# aw_201_clock.net
KiCad netlist of a schematic drawn in EAGLE
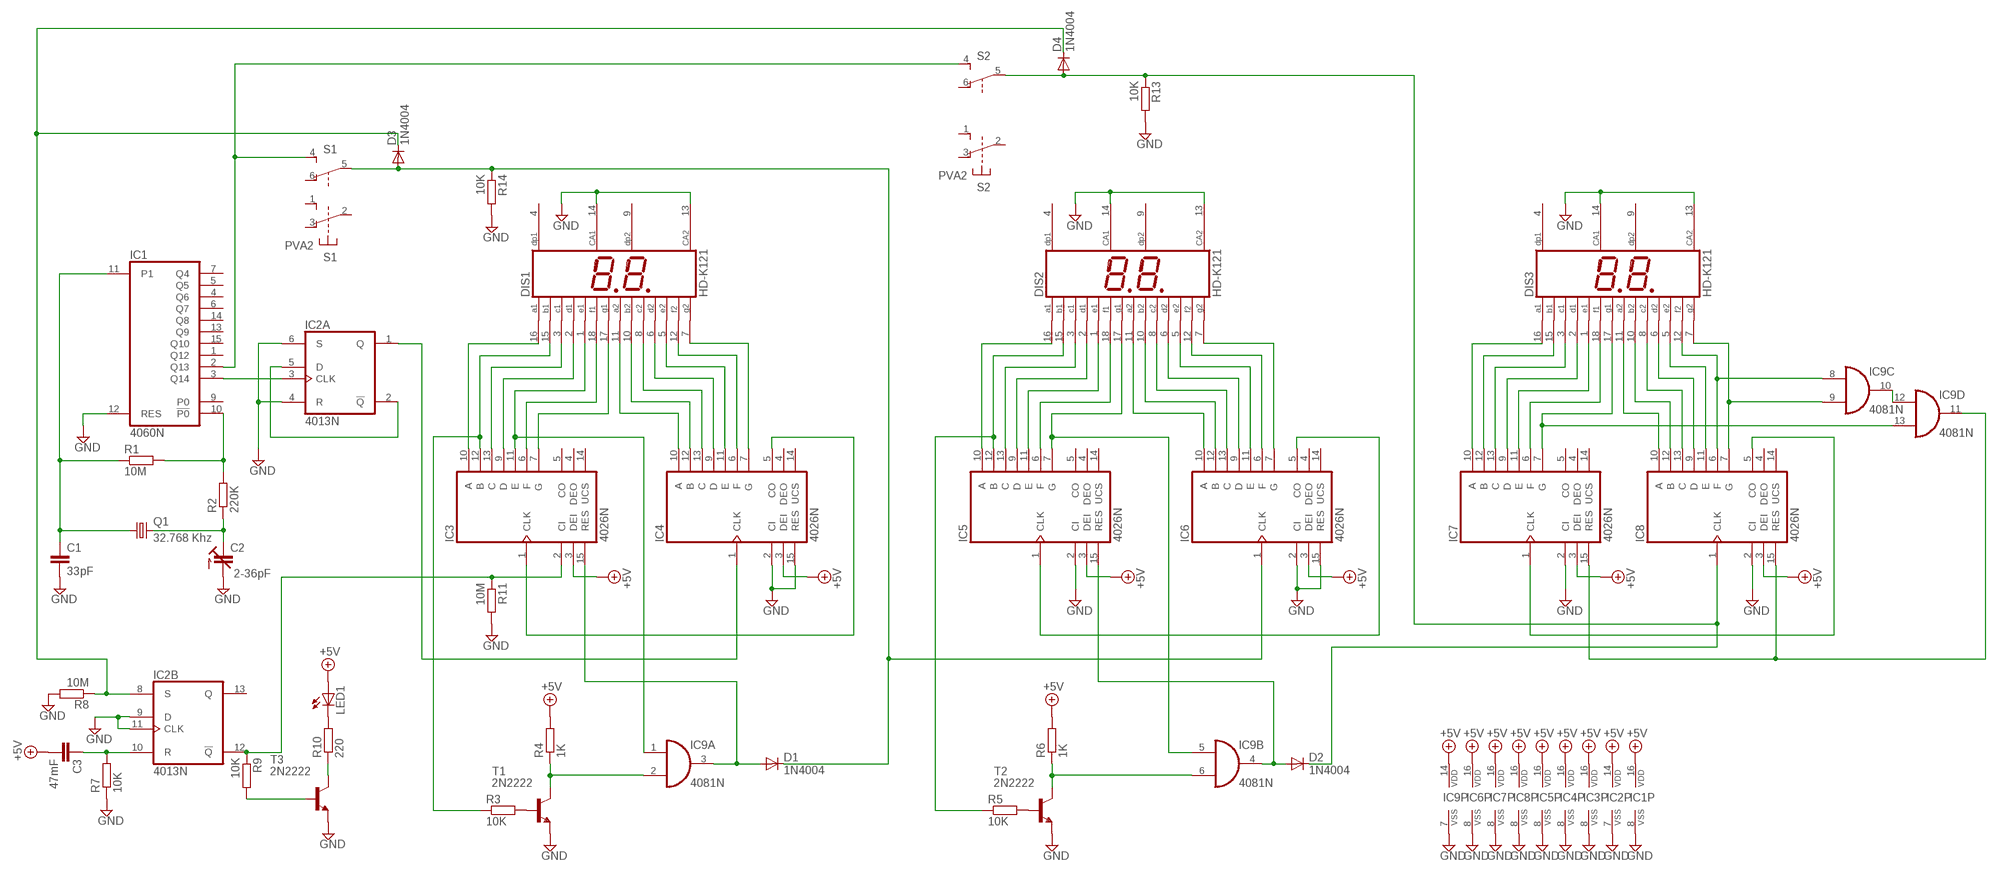
[diagram p0: schematic, sheet 1]

(export (version "E")
  (design (tool "Eeschema 10.0.6"))
  (components
    (comp (ref "C1")
      (value "33pF")
      (footprint "eagle-import:C050-024X044")
      (libsource (lib "eagle-import") (part "C-EU050-024X044"))
    )
    (comp (ref "C2")
      (value "2-36pF")
      (footprint "eagle-import:CTRIM3050.504")
      (libsource (lib "eagle-import") (part "C-TRIMM3050.504"))
    )
    (comp (ref "C3")
      (value "47mF")
      (footprint "eagle-import:C050-024X044")
      (libsource (lib "eagle-import") (part "C-EU050-024X044"))
    )
    (comp (ref "D1")
      (value "1N4004")
      (footprint "eagle-import:DO41-10")
      (libsource (lib "eagle-import") (part "1N4004"))
    )
    (comp (ref "D2")
      (value "1N4004")
      (footprint "eagle-import:DO41-10")
      (libsource (lib "eagle-import") (part "1N4004"))
    )
    (comp (ref "D3")
      (value "1N4004")
      (footprint "eagle-import:DO41-10")
      (libsource (lib "eagle-import") (part "1N4004"))
    )
    (comp (ref "D4")
      (value "1N4004")
      (footprint "eagle-import:DO41-10")
      (libsource (lib "eagle-import") (part "1N4004"))
    )
    (comp (ref "DIS1")
      (value "HD-K121")
      (footprint "eagle-import:HDSP-R")
      (libsource (lib "eagle-import") (part "HD-K121"))
    )
    (comp (ref "DIS2")
      (value "HD-K121")
      (footprint "eagle-import:HDSP-R")
      (libsource (lib "eagle-import") (part "HD-K121"))
    )
    (comp (ref "DIS3")
      (value "HD-K121")
      (footprint "eagle-import:HDSP-R")
      (libsource (lib "eagle-import") (part "HD-K121"))
    )
    (comp (ref "IC1")
      (value "4060N")
      (footprint "eagle-import:DIL16")
      (libsource (lib "eagle-import") (part "4060N"))
    )
    (comp (ref "IC2")
      (value "4013N")
      (footprint "eagle-import:DIL14")
      (libsource (lib "eagle-import") (part "4013N"))
    )
    (comp (ref "IC3")
      (value "4026N")
      (footprint "eagle-import:DIL16")
      (libsource (lib "eagle-import") (part "4026N"))
    )
    (comp (ref "IC4")
      (value "4026N")
      (footprint "eagle-import:DIL16")
      (libsource (lib "eagle-import") (part "4026N"))
    )
    (comp (ref "IC5")
      (value "4026N")
      (footprint "eagle-import:DIL16")
      (libsource (lib "eagle-import") (part "4026N"))
    )
    (comp (ref "IC6")
      (value "4026N")
      (footprint "eagle-import:DIL16")
      (libsource (lib "eagle-import") (part "4026N"))
    )
    (comp (ref "IC7")
      (value "4026N")
      (footprint "eagle-import:DIL16")
      (libsource (lib "eagle-import") (part "4026N"))
    )
    (comp (ref "IC8")
      (value "4026N")
      (footprint "eagle-import:DIL16")
      (libsource (lib "eagle-import") (part "4026N"))
    )
    (comp (ref "IC9")
      (value "4081N")
      (footprint "eagle-import:DIL14")
      (libsource (lib "eagle-import") (part "4081N"))
    )
    (comp (ref "LED1")
      (value "LED5MM")
      (footprint "eagle-import:LED5MM")
      (libsource (lib "eagle-import") (part "LED5MM"))
    )
    (comp (ref "Q1")
      (value "32.768 Khz")
      (footprint "eagle-import:TC26V")
      (libsource (lib "eagle-import") (part "CRYSTALTC26V"))
    )
    (comp (ref "R1")
      (value "10M")
      (footprint "eagle-import:0207_10")
      (libsource (lib "eagle-import") (part "R-EU_0207/10"))
    )
    (comp (ref "R2")
      (value "220K")
      (footprint "eagle-import:0207_10")
      (libsource (lib "eagle-import") (part "R-EU_0207/10"))
    )
    (comp (ref "R3")
      (value "10K")
      (footprint "eagle-import:0207_10")
      (libsource (lib "eagle-import") (part "R-EU_0207/10"))
    )
    (comp (ref "R4")
      (value "1K")
      (footprint "eagle-import:0207_10")
      (libsource (lib "eagle-import") (part "R-EU_0207/10"))
    )
    (comp (ref "R5")
      (value "10K")
      (footprint "eagle-import:0207_10")
      (libsource (lib "eagle-import") (part "R-EU_0207/10"))
    )
    (comp (ref "R6")
      (value "1K")
      (footprint "eagle-import:0207_10")
      (libsource (lib "eagle-import") (part "R-EU_0207/10"))
    )
    (comp (ref "R7")
      (value "10K")
      (footprint "eagle-import:0207_10")
      (libsource (lib "eagle-import") (part "R-EU_0207/10"))
    )
    (comp (ref "R8")
      (value "10M")
      (footprint "eagle-import:0207_10")
      (libsource (lib "eagle-import") (part "R-EU_0207/10"))
    )
    (comp (ref "R9")
      (value "10K")
      (footprint "eagle-import:0207_10")
      (libsource (lib "eagle-import") (part "R-EU_0207/10"))
    )
    (comp (ref "R10")
      (value "220")
      (footprint "eagle-import:0207_10")
      (libsource (lib "eagle-import") (part "R-EU_0207/10"))
    )
    (comp (ref "R11")
      (value "10M")
      (footprint "eagle-import:0207_10")
      (libsource (lib "eagle-import") (part "R-EU_0207/10"))
    )
    (comp (ref "R13")
      (value "10K")
      (footprint "eagle-import:0207_10")
      (libsource (lib "eagle-import") (part "R-EU_0207/10"))
    )
    (comp (ref "R14")
      (value "10K")
      (footprint "eagle-import:0207_10")
      (libsource (lib "eagle-import") (part "R-EU_0207/10"))
    )
    (comp (ref "S1")
      (value "PVA2")
      (footprint "eagle-import:PVA2F")
      (libsource (lib "eagle-import") (part "PVA2"))
    )
    (comp (ref "S2")
      (value "PVA2")
      (footprint "eagle-import:PVA2F")
      (libsource (lib "eagle-import") (part "PVA2"))
    )
    (comp (ref "T1")
      (value "2N2222")
      (footprint "eagle-import:TO18")
      (libsource (lib "eagle-import") (part "2N2222"))
    )
    (comp (ref "T2")
      (value "2N2222")
      (footprint "eagle-import:TO18")
      (libsource (lib "eagle-import") (part "2N2222"))
    )
    (comp (ref "T3")
      (value "2N2222")
      (footprint "eagle-import:TO18")
      (libsource (lib "eagle-import") (part "2N2222"))
    )
  )
  (nets
    (net (code "1") (name "+5V") (class "Default")
      (node (ref "C3") (pin "2") (pinfunction "2_2") (pintype "passive"))
      (node (ref "IC1") (pin "16") (pinfunction "VDD_16") (pintype "power_in"))
      (node (ref "IC2") (pin "14") (pinfunction "VDD_14") (pintype "power_in"))
      (node (ref "IC3") (pin "16") (pinfunction "VDD_16") (pintype "power_in"))
      (node (ref "IC3") (pin "3") (pinfunction "DEI_3") (pintype "input"))
      (node (ref "IC4") (pin "16") (pinfunction "VDD_16") (pintype "power_in"))
      (node (ref "IC4") (pin "3") (pinfunction "DEI_3") (pintype "input"))
      (node (ref "IC5") (pin "16") (pinfunction "VDD_16") (pintype "power_in"))
      (node (ref "IC5") (pin "3") (pinfunction "DEI_3") (pintype "input"))
      (node (ref "IC6") (pin "16") (pinfunction "VDD_16") (pintype "power_in"))
      (node (ref "IC6") (pin "3") (pinfunction "DEI_3") (pintype "input"))
      (node (ref "IC7") (pin "16") (pinfunction "VDD_16") (pintype "power_in"))
      (node (ref "IC7") (pin "3") (pinfunction "DEI_3") (pintype "input"))
      (node (ref "IC8") (pin "16") (pinfunction "VDD_16") (pintype "power_in"))
      (node (ref "IC8") (pin "3") (pinfunction "DEI_3") (pintype "input"))
      (node (ref "IC9") (pin "14") (pinfunction "VDD_14") (pintype "power_in"))
      (node (ref "LED1") (pin "A") (pinfunction "A_A") (pintype "passive"))
      (node (ref "R4") (pin "2") (pinfunction "2_2") (pintype "passive"))
      (node (ref "R6") (pin "2") (pinfunction "2_2") (pintype "passive"))
    )
    (net (code "2") (name "GND") (class "Default")
      (node (ref "C1") (pin "2") (pinfunction "2_2") (pintype "passive"))
      (node (ref "C2") (pin "2") (pinfunction "A_2") (pintype "passive"))
      (node (ref "DIS1") (pin "13") (pinfunction "CA2_13") (pintype "passive"))
      (node (ref "DIS1") (pin "14") (pinfunction "CA1_14") (pintype "passive"))
      (node (ref "DIS2") (pin "13") (pinfunction "CA2_13") (pintype "passive"))
      (node (ref "DIS2") (pin "14") (pinfunction "CA1_14") (pintype "passive"))
      (node (ref "DIS3") (pin "13") (pinfunction "CA2_13") (pintype "passive"))
      (node (ref "DIS3") (pin "14") (pinfunction "CA1_14") (pintype "passive"))
      (node (ref "IC1") (pin "12") (pinfunction "RES_12") (pintype "input"))
      (node (ref "IC1") (pin "8") (pinfunction "VSS_8") (pintype "power_in"))
      (node (ref "IC2") (pin "11") (pinfunction "CLK_11") (pintype "input"))
      (node (ref "IC2") (pin "4") (pinfunction "R_4") (pintype "input"))
      (node (ref "IC2") (pin "6") (pinfunction "S_6") (pintype "input"))
      (node (ref "IC2") (pin "7") (pinfunction "VSS_7") (pintype "power_in"))
      (node (ref "IC2") (pin "9") (pinfunction "D_9") (pintype "input"))
      (node (ref "IC3") (pin "8") (pinfunction "VSS_8") (pintype "power_in"))
      (node (ref "IC4") (pin "15") (pinfunction "RES_15") (pintype "input"))
      (node (ref "IC4") (pin "2") (pinfunction "CI_2") (pintype "input"))
      (node (ref "IC4") (pin "8") (pinfunction "VSS_8") (pintype "power_in"))
      (node (ref "IC5") (pin "2") (pinfunction "CI_2") (pintype "input"))
      (node (ref "IC5") (pin "8") (pinfunction "VSS_8") (pintype "power_in"))
      (node (ref "IC6") (pin "15") (pinfunction "RES_15") (pintype "input"))
      (node (ref "IC6") (pin "2") (pinfunction "CI_2") (pintype "input"))
      (node (ref "IC6") (pin "8") (pinfunction "VSS_8") (pintype "power_in"))
      (node (ref "IC7") (pin "2") (pinfunction "CI_2") (pintype "input"))
      (node (ref "IC7") (pin "8") (pinfunction "VSS_8") (pintype "power_in"))
      (node (ref "IC8") (pin "2") (pinfunction "CI_2") (pintype "input"))
      (node (ref "IC8") (pin "8") (pinfunction "VSS_8") (pintype "power_in"))
      (node (ref "IC9") (pin "7") (pinfunction "VSS_7") (pintype "power_in"))
      (node (ref "R11") (pin "2") (pinfunction "2_2") (pintype "passive"))
      (node (ref "R13") (pin "2") (pinfunction "2_2") (pintype "passive"))
      (node (ref "R14") (pin "2") (pinfunction "2_2") (pintype "passive"))
      (node (ref "R7") (pin "1") (pinfunction "1_1") (pintype "passive"))
      (node (ref "R8") (pin "2") (pinfunction "2_2") (pintype "passive"))
      (node (ref "T1") (pin "1") (pinfunction "E_1") (pintype "passive"))
      (node (ref "T2") (pin "1") (pinfunction "E_1") (pintype "passive"))
      (node (ref "T3") (pin "1") (pinfunction "E_1") (pintype "passive"))
    )
    (net (code "3") (name "Net-(C2-E)") (class "Default")
      (node (ref "C2") (pin "1") (pinfunction "E_1") (pintype "passive"))
      (node (ref "Q1") (pin "2") (pinfunction "2_2") (pintype "passive"))
      (node (ref "R2") (pin "1") (pinfunction "1_1") (pintype "passive"))
    )
    (net (code "4") (name "Net-(DIS1-A1)") (class "Default")
      (node (ref "DIS1") (pin "16") (pinfunction "A1_16") (pintype "passive"))
      (node (ref "IC3") (pin "10") (pinfunction "A_10") (pintype "output"))
    )
    (net (code "5") (name "Net-(DIS1-A2)") (class "Default")
      (node (ref "DIS1") (pin "11") (pinfunction "A2_11") (pintype "passive"))
      (node (ref "IC4") (pin "10") (pinfunction "A_10") (pintype "output"))
    )
    (net (code "6") (name "Net-(DIS1-B1)") (class "Default")
      (node (ref "DIS1") (pin "15") (pinfunction "B1_15") (pintype "passive"))
      (node (ref "IC3") (pin "12") (pinfunction "B_12") (pintype "output"))
      (node (ref "R3") (pin "1") (pinfunction "1_1") (pintype "passive"))
    )
    (net (code "7") (name "Net-(DIS1-B2)") (class "Default")
      (node (ref "DIS1") (pin "10") (pinfunction "B2_10") (pintype "passive"))
      (node (ref "IC4") (pin "12") (pinfunction "B_12") (pintype "output"))
    )
    (net (code "8") (name "Net-(DIS1-C1)") (class "Default")
      (node (ref "DIS1") (pin "3") (pinfunction "C1_3") (pintype "passive"))
      (node (ref "IC3") (pin "13") (pinfunction "C_13") (pintype "output"))
    )
    (net (code "9") (name "Net-(DIS1-C2)") (class "Default")
      (node (ref "DIS1") (pin "8") (pinfunction "C2_8") (pintype "passive"))
      (node (ref "IC4") (pin "13") (pinfunction "C_13") (pintype "output"))
    )
    (net (code "10") (name "Net-(DIS1-D1)") (class "Default")
      (node (ref "DIS1") (pin "2") (pinfunction "D1_2") (pintype "passive"))
      (node (ref "IC3") (pin "9") (pinfunction "D_9") (pintype "output"))
    )
    (net (code "11") (name "Net-(DIS1-D2)") (class "Default")
      (node (ref "DIS1") (pin "6") (pinfunction "D2_6") (pintype "passive"))
      (node (ref "IC4") (pin "9") (pinfunction "D_9") (pintype "output"))
    )
    (net (code "12") (name "Net-(DIS1-E1)") (class "Default")
      (node (ref "DIS1") (pin "1") (pinfunction "E1_1") (pintype "passive"))
      (node (ref "IC3") (pin "11") (pinfunction "E_11") (pintype "output"))
      (node (ref "IC9") (pin "1") (pinfunction "I0_1") (pintype "input"))
    )
    (net (code "13") (name "Net-(DIS1-E2)") (class "Default")
      (node (ref "DIS1") (pin "5") (pinfunction "E2_5") (pintype "passive"))
      (node (ref "IC4") (pin "11") (pinfunction "E_11") (pintype "output"))
    )
    (net (code "14") (name "Net-(DIS1-F1)") (class "Default")
      (node (ref "DIS1") (pin "18") (pinfunction "F1_18") (pintype "passive"))
      (node (ref "IC3") (pin "6") (pinfunction "F_6") (pintype "output"))
    )
    (net (code "15") (name "Net-(DIS1-F2)") (class "Default")
      (node (ref "DIS1") (pin "12") (pinfunction "F2_12") (pintype "passive"))
      (node (ref "IC4") (pin "6") (pinfunction "F_6") (pintype "output"))
    )
    (net (code "16") (name "Net-(DIS1-G1)") (class "Default")
      (node (ref "DIS1") (pin "17") (pinfunction "G1_17") (pintype "passive"))
      (node (ref "IC3") (pin "7") (pinfunction "G_7") (pintype "output"))
    )
    (net (code "17") (name "Net-(DIS1-G2)") (class "Default")
      (node (ref "DIS1") (pin "7") (pinfunction "G2_7") (pintype "passive"))
      (node (ref "IC4") (pin "7") (pinfunction "G_7") (pintype "output"))
    )
    (net (code "18") (name "Net-(DIS2-A1)") (class "Default")
      (node (ref "DIS2") (pin "16") (pinfunction "A1_16") (pintype "passive"))
      (node (ref "IC5") (pin "10") (pinfunction "A_10") (pintype "output"))
    )
    (net (code "19") (name "Net-(DIS2-A2)") (class "Default")
      (node (ref "DIS2") (pin "11") (pinfunction "A2_11") (pintype "passive"))
      (node (ref "IC6") (pin "10") (pinfunction "A_10") (pintype "output"))
    )
    (net (code "20") (name "Net-(DIS2-B1)") (class "Default")
      (node (ref "DIS2") (pin "15") (pinfunction "B1_15") (pintype "passive"))
      (node (ref "IC5") (pin "12") (pinfunction "B_12") (pintype "output"))
      (node (ref "R5") (pin "1") (pinfunction "1_1") (pintype "passive"))
    )
    (net (code "21") (name "Net-(DIS2-B2)") (class "Default")
      (node (ref "DIS2") (pin "10") (pinfunction "B2_10") (pintype "passive"))
      (node (ref "IC6") (pin "12") (pinfunction "B_12") (pintype "output"))
    )
    (net (code "22") (name "Net-(DIS2-C1)") (class "Default")
      (node (ref "DIS2") (pin "3") (pinfunction "C1_3") (pintype "passive"))
      (node (ref "IC5") (pin "13") (pinfunction "C_13") (pintype "output"))
    )
    (net (code "23") (name "Net-(DIS2-C2)") (class "Default")
      (node (ref "DIS2") (pin "8") (pinfunction "C2_8") (pintype "passive"))
      (node (ref "IC6") (pin "13") (pinfunction "C_13") (pintype "output"))
    )
    (net (code "24") (name "Net-(DIS2-D1)") (class "Default")
      (node (ref "DIS2") (pin "2") (pinfunction "D1_2") (pintype "passive"))
      (node (ref "IC5") (pin "9") (pinfunction "D_9") (pintype "output"))
    )
    (net (code "25") (name "Net-(DIS2-D2)") (class "Default")
      (node (ref "DIS2") (pin "6") (pinfunction "D2_6") (pintype "passive"))
      (node (ref "IC6") (pin "9") (pinfunction "D_9") (pintype "output"))
    )
    (net (code "26") (name "Net-(DIS2-E1)") (class "Default")
      (node (ref "DIS2") (pin "1") (pinfunction "E1_1") (pintype "passive"))
      (node (ref "IC5") (pin "11") (pinfunction "E_11") (pintype "output"))
    )
    (net (code "27") (name "Net-(DIS2-E2)") (class "Default")
      (node (ref "DIS2") (pin "5") (pinfunction "E2_5") (pintype "passive"))
      (node (ref "IC6") (pin "11") (pinfunction "E_11") (pintype "output"))
    )
    (net (code "28") (name "Net-(DIS2-F1)") (class "Default")
      (node (ref "DIS2") (pin "18") (pinfunction "F1_18") (pintype "passive"))
      (node (ref "IC5") (pin "6") (pinfunction "F_6") (pintype "output"))
    )
    (net (code "29") (name "Net-(DIS2-F2)") (class "Default")
      (node (ref "DIS2") (pin "12") (pinfunction "F2_12") (pintype "passive"))
      (node (ref "IC6") (pin "6") (pinfunction "F_6") (pintype "output"))
    )
    (net (code "30") (name "Net-(DIS2-G1)") (class "Default")
      (node (ref "DIS2") (pin "17") (pinfunction "G1_17") (pintype "passive"))
      (node (ref "IC5") (pin "7") (pinfunction "G_7") (pintype "output"))
      (node (ref "IC9") (pin "5") (pinfunction "I0_5") (pintype "input"))
    )
    (net (code "31") (name "Net-(DIS2-G2)") (class "Default")
      (node (ref "DIS2") (pin "7") (pinfunction "G2_7") (pintype "passive"))
      (node (ref "IC6") (pin "7") (pinfunction "G_7") (pintype "output"))
    )
    (net (code "32") (name "Net-(DIS3-A1)") (class "Default")
      (node (ref "DIS3") (pin "16") (pinfunction "A1_16") (pintype "passive"))
      (node (ref "IC7") (pin "10") (pinfunction "A_10") (pintype "output"))
    )
    (net (code "33") (name "Net-(DIS3-A2)") (class "Default")
      (node (ref "DIS3") (pin "11") (pinfunction "A2_11") (pintype "passive"))
      (node (ref "IC8") (pin "10") (pinfunction "A_10") (pintype "output"))
    )
    (net (code "34") (name "Net-(DIS3-B1)") (class "Default")
      (node (ref "DIS3") (pin "15") (pinfunction "B1_15") (pintype "passive"))
      (node (ref "IC7") (pin "12") (pinfunction "B_12") (pintype "output"))
    )
    (net (code "35") (name "Net-(DIS3-B2)") (class "Default")
      (node (ref "DIS3") (pin "10") (pinfunction "B2_10") (pintype "passive"))
      (node (ref "IC8") (pin "12") (pinfunction "B_12") (pintype "output"))
    )
    (net (code "36") (name "Net-(DIS3-C1)") (class "Default")
      (node (ref "DIS3") (pin "3") (pinfunction "C1_3") (pintype "passive"))
      (node (ref "IC7") (pin "13") (pinfunction "C_13") (pintype "output"))
    )
    (net (code "37") (name "Net-(DIS3-C2)") (class "Default")
      (node (ref "DIS3") (pin "8") (pinfunction "C2_8") (pintype "passive"))
      (node (ref "IC8") (pin "13") (pinfunction "C_13") (pintype "output"))
    )
    (net (code "38") (name "Net-(DIS3-D1)") (class "Default")
      (node (ref "DIS3") (pin "2") (pinfunction "D1_2") (pintype "passive"))
      (node (ref "IC7") (pin "9") (pinfunction "D_9") (pintype "output"))
    )
    (net (code "39") (name "Net-(DIS3-D2)") (class "Default")
      (node (ref "DIS3") (pin "6") (pinfunction "D2_6") (pintype "passive"))
      (node (ref "IC8") (pin "9") (pinfunction "D_9") (pintype "output"))
    )
    (net (code "40") (name "Net-(DIS3-E1)") (class "Default")
      (node (ref "DIS3") (pin "1") (pinfunction "E1_1") (pintype "passive"))
      (node (ref "IC7") (pin "11") (pinfunction "E_11") (pintype "output"))
    )
    (net (code "41") (name "Net-(DIS3-E2)") (class "Default")
      (node (ref "DIS3") (pin "5") (pinfunction "E2_5") (pintype "passive"))
      (node (ref "IC8") (pin "11") (pinfunction "E_11") (pintype "output"))
    )
    (net (code "42") (name "Net-(DIS3-F1)") (class "Default")
      (node (ref "DIS3") (pin "18") (pinfunction "F1_18") (pintype "passive"))
      (node (ref "IC7") (pin "6") (pinfunction "F_6") (pintype "output"))
    )
    (net (code "43") (name "Net-(DIS3-F2)") (class "Default")
      (node (ref "DIS3") (pin "12") (pinfunction "F2_12") (pintype "passive"))
      (node (ref "IC8") (pin "6") (pinfunction "F_6") (pintype "output"))
      (node (ref "IC9") (pin "8") (pinfunction "I0_8") (pintype "input"))
    )
    (net (code "44") (name "Net-(DIS3-G1)") (class "Default")
      (node (ref "DIS3") (pin "17") (pinfunction "G1_17") (pintype "passive"))
      (node (ref "IC7") (pin "7") (pinfunction "G_7") (pintype "output"))
      (node (ref "IC9") (pin "13") (pinfunction "I1_13") (pintype "input"))
    )
    (net (code "45") (name "Net-(DIS3-G2)") (class "Default")
      (node (ref "DIS3") (pin "7") (pinfunction "G2_7") (pintype "passive"))
      (node (ref "IC8") (pin "7") (pinfunction "G_7") (pintype "output"))
      (node (ref "IC9") (pin "9") (pinfunction "I1_9") (pintype "input"))
    )
    (net (code "46") (name "Net-(IC1A-P1)") (class "Default")
      (node (ref "C1") (pin "1") (pinfunction "1_1") (pintype "passive"))
      (node (ref "IC1") (pin "11") (pinfunction "P1_11") (pintype "input"))
      (node (ref "Q1") (pin "1") (pinfunction "1_1") (pintype "passive"))
      (node (ref "R1") (pin "1") (pinfunction "1_1") (pintype "passive"))
    )
    (net (code "47") (name "Net-(IC1A-Q13)") (class "Default")
      (node (ref "IC1") (pin "2") (pinfunction "Q13_2") (pintype "output"))
      (node (ref "S1") (pin "4") (pinfunction "S_4") (pintype "passive"))
      (node (ref "S2") (pin "4") (pinfunction "S_4") (pintype "passive"))
    )
    (net (code "48") (name "Net-(IC1A-Q14)") (class "Default")
      (node (ref "IC1") (pin "3") (pinfunction "Q14_3") (pintype "output"))
      (node (ref "IC2") (pin "3") (pinfunction "CLK_3") (pintype "input"))
    )
    (net (code "49") (name "Net-(IC1A-~{P0})") (class "Default")
      (node (ref "IC1") (pin "10") (pinfunction "~{P0}_10") (pintype "output"))
      (node (ref "R1") (pin "2") (pinfunction "2_2") (pintype "passive"))
      (node (ref "R2") (pin "2") (pinfunction "2_2") (pintype "passive"))
    )
    (net (code "50") (name "Net-(IC2A-D)") (class "Default")
      (node (ref "IC2") (pin "2") (pinfunction "~{Q}_2") (pintype "output"))
      (node (ref "IC2") (pin "5") (pinfunction "D_5") (pintype "input"))
    )
    (net (code "51") (name "Net-(IC2A-Q)") (class "Default")
      (node (ref "IC2") (pin "1") (pinfunction "Q_1") (pintype "output"))
      (node (ref "IC4") (pin "1") (pinfunction "CLK_1") (pintype "input"))
    )
    (net (code "52") (name "Net-(IC2B-R)") (class "Default")
      (node (ref "C3") (pin "1") (pinfunction "1_1") (pintype "passive"))
      (node (ref "IC2") (pin "10") (pinfunction "R_10") (pintype "input"))
      (node (ref "R7") (pin "2") (pinfunction "2_2") (pintype "passive"))
    )
    (net (code "53") (name "Net-(IC2B-S)") (class "Default")
      (node (ref "D3") (pin "C") (pinfunction "C_C") (pintype "passive"))
      (node (ref "D4") (pin "C") (pinfunction "C_C") (pintype "passive"))
      (node (ref "IC2") (pin "8") (pinfunction "S_8") (pintype "input"))
      (node (ref "R8") (pin "1") (pinfunction "1_1") (pintype "passive"))
    )
    (net (code "54") (name "Net-(IC2B-~{Q})") (class "Default")
      (node (ref "IC2") (pin "12") (pinfunction "~{Q}_12") (pintype "output"))
      (node (ref "IC3") (pin "2") (pinfunction "CI_2") (pintype "input"))
      (node (ref "R11") (pin "1") (pinfunction "1_1") (pintype "passive"))
      (node (ref "R9") (pin "1") (pinfunction "1_1") (pintype "passive"))
    )
    (net (code "55") (name "Net-(IC3A-CLK)") (class "Default")
      (node (ref "IC3") (pin "1") (pinfunction "CLK_1") (pintype "input"))
      (node (ref "IC4") (pin "5") (pinfunction "CO_5") (pintype "output"))
    )
    (net (code "56") (name "Net-(IC3A-RES)") (class "Default")
      (node (ref "D1") (pin "A") (pinfunction "A_A") (pintype "passive"))
      (node (ref "IC3") (pin "15") (pinfunction "RES_15") (pintype "input"))
      (node (ref "IC9") (pin "3") (pinfunction "O_3") (pintype "output"))
    )
    (net (code "57") (name "Net-(IC5A-CLK)") (class "Default")
      (node (ref "IC5") (pin "1") (pinfunction "CLK_1") (pintype "input"))
      (node (ref "IC6") (pin "5") (pinfunction "CO_5") (pintype "output"))
    )
    (net (code "58") (name "Net-(IC5A-RES)") (class "Default")
      (node (ref "D2") (pin "A") (pinfunction "A_A") (pintype "passive"))
      (node (ref "IC5") (pin "15") (pinfunction "RES_15") (pintype "input"))
      (node (ref "IC9") (pin "4") (pinfunction "O_4") (pintype "output"))
    )
    (net (code "59") (name "Net-(IC6A-CLK)") (class "Default")
      (node (ref "D1") (pin "C") (pinfunction "C_C") (pintype "passive"))
      (node (ref "D3") (pin "A") (pinfunction "A_A") (pintype "passive"))
      (node (ref "IC6") (pin "1") (pinfunction "CLK_1") (pintype "input"))
      (node (ref "R14") (pin "1") (pinfunction "1_1") (pintype "passive"))
      (node (ref "S1") (pin "5") (pinfunction "P_5") (pintype "passive"))
    )
    (net (code "60") (name "Net-(IC7A-CLK)") (class "Default")
      (node (ref "IC7") (pin "1") (pinfunction "CLK_1") (pintype "input"))
      (node (ref "IC8") (pin "5") (pinfunction "CO_5") (pintype "output"))
    )
    (net (code "61") (name "Net-(IC7A-RES)") (class "Default")
      (node (ref "IC7") (pin "15") (pinfunction "RES_15") (pintype "input"))
      (node (ref "IC8") (pin "15") (pinfunction "RES_15") (pintype "input"))
      (node (ref "IC9") (pin "11") (pinfunction "O_11") (pintype "output"))
    )
    (net (code "62") (name "Net-(IC8A-CLK)") (class "Default")
      (node (ref "D2") (pin "C") (pinfunction "C_C") (pintype "passive"))
      (node (ref "D4") (pin "A") (pinfunction "A_A") (pintype "passive"))
      (node (ref "IC8") (pin "1") (pinfunction "CLK_1") (pintype "input"))
      (node (ref "R13") (pin "1") (pinfunction "1_1") (pintype "passive"))
      (node (ref "S2") (pin "5") (pinfunction "P_5") (pintype "passive"))
    )
    (net (code "63") (name "Net-(IC9A-I1)") (class "Default")
      (node (ref "IC9") (pin "2") (pinfunction "I1_2") (pintype "input"))
      (node (ref "R4") (pin "1") (pinfunction "1_1") (pintype "passive"))
      (node (ref "T1") (pin "3") (pinfunction "C_3") (pintype "passive"))
    )
    (net (code "64") (name "Net-(IC9B-I1)") (class "Default")
      (node (ref "IC9") (pin "6") (pinfunction "I1_6") (pintype "input"))
      (node (ref "R6") (pin "1") (pinfunction "1_1") (pintype "passive"))
      (node (ref "T2") (pin "3") (pinfunction "C_3") (pintype "passive"))
    )
    (net (code "65") (name "Net-(IC9C-O)") (class "Default")
      (node (ref "IC9") (pin "10") (pinfunction "O_10") (pintype "output"))
      (node (ref "IC9") (pin "12") (pinfunction "I0_12") (pintype "input"))
    )
    (net (code "66") (name "Net-(LED1-C)") (class "Default")
      (node (ref "LED1") (pin "K") (pinfunction "C_K") (pintype "passive"))
      (node (ref "R10") (pin "2") (pinfunction "2_2") (pintype "passive"))
    )
    (net (code "67") (name "Net-(T1-B)") (class "Default")
      (node (ref "R3") (pin "2") (pinfunction "2_2") (pintype "passive"))
      (node (ref "T1") (pin "2") (pinfunction "B_2") (pintype "passive"))
    )
    (net (code "68") (name "Net-(T2-B)") (class "Default")
      (node (ref "R5") (pin "2") (pinfunction "2_2") (pintype "passive"))
      (node (ref "T2") (pin "2") (pinfunction "B_2") (pintype "passive"))
    )
    (net (code "69") (name "Net-(T3-B)") (class "Default")
      (node (ref "R9") (pin "2") (pinfunction "2_2") (pintype "passive"))
      (node (ref "T3") (pin "2") (pinfunction "B_2") (pintype "passive"))
    )
    (net (code "70") (name "Net-(T3-C)") (class "Default")
      (node (ref "R10") (pin "1") (pinfunction "1_1") (pintype "passive"))
      (node (ref "T3") (pin "3") (pinfunction "C_3") (pintype "passive"))
    )
    (net (code "71") (name "unconnected-(DIS1-DP1-Pad4)") (class "Default")
      (node (ref "DIS1") (pin "4") (pinfunction "DP1_4") (pintype "passive"))
    )
    (net (code "72") (name "unconnected-(DIS1-DP2-Pad9)") (class "Default")
      (node (ref "DIS1") (pin "9") (pinfunction "DP2_9") (pintype "passive"))
    )
    (net (code "73") (name "unconnected-(DIS2-DP1-Pad4)") (class "Default")
      (node (ref "DIS2") (pin "4") (pinfunction "DP1_4") (pintype "passive"))
    )
    (net (code "74") (name "unconnected-(DIS2-DP2-Pad9)") (class "Default")
      (node (ref "DIS2") (pin "9") (pinfunction "DP2_9") (pintype "passive"))
    )
    (net (code "75") (name "unconnected-(DIS3-DP1-Pad4)") (class "Default")
      (node (ref "DIS3") (pin "4") (pinfunction "DP1_4") (pintype "passive"))
    )
    (net (code "76") (name "unconnected-(DIS3-DP2-Pad9)") (class "Default")
      (node (ref "DIS3") (pin "9") (pinfunction "DP2_9") (pintype "passive"))
    )
    (net (code "77") (name "unconnected-(IC1A-P0-Pad9)") (class "Default")
      (node (ref "IC1") (pin "9") (pinfunction "P0_9") (pintype "output"))
    )
    (net (code "78") (name "unconnected-(IC1A-Q4-Pad7)") (class "Default")
      (node (ref "IC1") (pin "7") (pinfunction "Q4_7") (pintype "output"))
    )
    (net (code "79") (name "unconnected-(IC1A-Q5-Pad5)") (class "Default")
      (node (ref "IC1") (pin "5") (pinfunction "Q5_5") (pintype "output"))
    )
    (net (code "80") (name "unconnected-(IC1A-Q6-Pad4)") (class "Default")
      (node (ref "IC1") (pin "4") (pinfunction "Q6_4") (pintype "output"))
    )
    (net (code "81") (name "unconnected-(IC1A-Q7-Pad6)") (class "Default")
      (node (ref "IC1") (pin "6") (pinfunction "Q7_6") (pintype "output"))
    )
    (net (code "82") (name "unconnected-(IC1A-Q8-Pad14)") (class "Default")
      (node (ref "IC1") (pin "14") (pinfunction "Q8_14") (pintype "output"))
    )
    (net (code "83") (name "unconnected-(IC1A-Q9-Pad13)") (class "Default")
      (node (ref "IC1") (pin "13") (pinfunction "Q9_13") (pintype "output"))
    )
    (net (code "84") (name "unconnected-(IC1A-Q10-Pad15)") (class "Default")
      (node (ref "IC1") (pin "15") (pinfunction "Q10_15") (pintype "output"))
    )
    (net (code "85") (name "unconnected-(IC1A-Q12-Pad1)") (class "Default")
      (node (ref "IC1") (pin "1") (pinfunction "Q12_1") (pintype "output"))
    )
    (net (code "86") (name "unconnected-(IC2B-Q-Pad13)") (class "Default")
      (node (ref "IC2") (pin "13") (pinfunction "Q_13") (pintype "output"))
    )
    (net (code "87") (name "unconnected-(IC3A-CO-Pad5)") (class "Default")
      (node (ref "IC3") (pin "5") (pinfunction "CO_5") (pintype "output"))
    )
    (net (code "88") (name "unconnected-(IC3A-DEO-Pad4)") (class "Default")
      (node (ref "IC3") (pin "4") (pinfunction "DEO_4") (pintype "output"))
    )
    (net (code "89") (name "unconnected-(IC3A-UCS-Pad14)") (class "Default")
      (node (ref "IC3") (pin "14") (pinfunction "UCS_14") (pintype "output"))
    )
    (net (code "90") (name "unconnected-(IC4A-DEO-Pad4)") (class "Default")
      (node (ref "IC4") (pin "4") (pinfunction "DEO_4") (pintype "output"))
    )
    (net (code "91") (name "unconnected-(IC4A-UCS-Pad14)") (class "Default")
      (node (ref "IC4") (pin "14") (pinfunction "UCS_14") (pintype "output"))
    )
    (net (code "92") (name "unconnected-(IC5A-CO-Pad5)") (class "Default")
      (node (ref "IC5") (pin "5") (pinfunction "CO_5") (pintype "output"))
    )
    (net (code "93") (name "unconnected-(IC5A-DEO-Pad4)") (class "Default")
      (node (ref "IC5") (pin "4") (pinfunction "DEO_4") (pintype "output"))
    )
    (net (code "94") (name "unconnected-(IC5A-UCS-Pad14)") (class "Default")
      (node (ref "IC5") (pin "14") (pinfunction "UCS_14") (pintype "output"))
    )
    (net (code "95") (name "unconnected-(IC6A-DEO-Pad4)") (class "Default")
      (node (ref "IC6") (pin "4") (pinfunction "DEO_4") (pintype "output"))
    )
    (net (code "96") (name "unconnected-(IC6A-UCS-Pad14)") (class "Default")
      (node (ref "IC6") (pin "14") (pinfunction "UCS_14") (pintype "output"))
    )
    (net (code "97") (name "unconnected-(IC7A-CO-Pad5)") (class "Default")
      (node (ref "IC7") (pin "5") (pinfunction "CO_5") (pintype "output"))
    )
    (net (code "98") (name "unconnected-(IC7A-DEO-Pad4)") (class "Default")
      (node (ref "IC7") (pin "4") (pinfunction "DEO_4") (pintype "output"))
    )
    (net (code "99") (name "unconnected-(IC7A-UCS-Pad14)") (class "Default")
      (node (ref "IC7") (pin "14") (pinfunction "UCS_14") (pintype "output"))
    )
    (net (code "100") (name "unconnected-(IC8A-DEO-Pad4)") (class "Default")
      (node (ref "IC8") (pin "4") (pinfunction "DEO_4") (pintype "output"))
    )
    (net (code "101") (name "unconnected-(IC8A-UCS-Pad14)") (class "Default")
      (node (ref "IC8") (pin "14") (pinfunction "UCS_14") (pintype "output"))
    )
    (net (code "102") (name "unconnected-(S1A-O-Pad3)") (class "Default")
      (node (ref "S1") (pin "3") (pinfunction "O_3") (pintype "passive"))
    )
    (net (code "103") (name "unconnected-(S1A-P-Pad2)") (class "Default")
      (node (ref "S1") (pin "2") (pinfunction "P_2") (pintype "passive"))
    )
    (net (code "104") (name "unconnected-(S1A-S-Pad1)") (class "Default")
      (node (ref "S1") (pin "1") (pinfunction "S_1") (pintype "passive"))
    )
    (net (code "105") (name "unconnected-(S1B-O-Pad6)") (class "Default")
      (node (ref "S1") (pin "6") (pinfunction "O_6") (pintype "passive"))
    )
    (net (code "106") (name "unconnected-(S2A-O-Pad3)") (class "Default")
      (node (ref "S2") (pin "3") (pinfunction "O_3") (pintype "passive"))
    )
    (net (code "107") (name "unconnected-(S2A-P-Pad2)") (class "Default")
      (node (ref "S2") (pin "2") (pinfunction "P_2") (pintype "passive"))
    )
    (net (code "108") (name "unconnected-(S2A-S-Pad1)") (class "Default")
      (node (ref "S2") (pin "1") (pinfunction "S_1") (pintype "passive"))
    )
    (net (code "109") (name "unconnected-(S2B-O-Pad6)") (class "Default")
      (node (ref "S2") (pin "6") (pinfunction "O_6") (pintype "passive"))
    )
  )
)
